# USB_PHY.net
KiCad netlist of a schematic drawn in Altium Designer
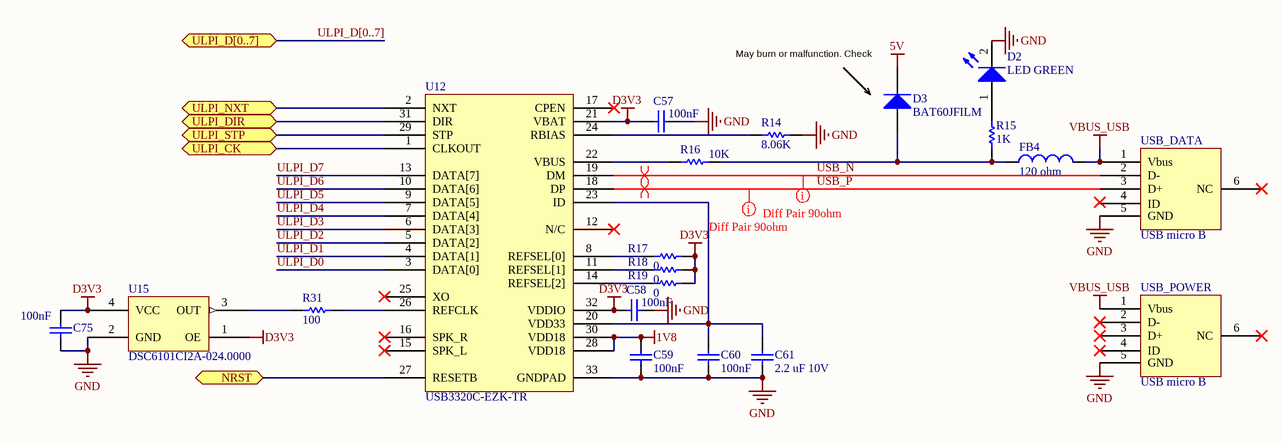
[diagram p0: USB PHY.SchDoc]

(export (version "E")
  (design (tool "Eeschema 10.0.6"))
  (components
    (comp (ref "C57")
      (value "100nF")
      (footprint "0603 Cap")
      (description "CAP CER 0.1UF 16V X7R 0603")
      (fields
        (field (name "MANUFACTURER") "KEMET")
        (field (name "MANUFACTURER PART NUMBER") "C0603C104K4RACTU")
      )
      (libsource (lib "Componentes_base") (part "C0603C104K4RACTU"))
    )
    (comp (ref "C58")
      (value "100nF")
      (footprint "0603 Cap")
      (description "CAP CER 0.1UF 16V X7R 0603")
      (fields
        (field (name "MANUFACTURER") "KEMET")
        (field (name "MANUFACTURER PART NUMBER") "C0603C104K4RACTU")
      )
      (libsource (lib "Componentes_base") (part "C0603C104K4RACTU"))
    )
    (comp (ref "C59")
      (value "100nF")
      (footprint "0603 Cap")
      (description "CAP CER 0.1UF 16V X7R 0603")
      (fields
        (field (name "MANUFACTURER") "KEMET")
        (field (name "MANUFACTURER PART NUMBER") "C0603C104K4RACTU")
      )
      (libsource (lib "Componentes_base") (part "C0603C104K4RACTU"))
    )
    (comp (ref "C60")
      (value "100nF")
      (footprint "0603 Cap")
      (description "CAP CER 0.1UF 16V X7R 0603")
      (fields
        (field (name "MANUFACTURER") "KEMET")
        (field (name "MANUFACTURER PART NUMBER") "C0603C104K4RACTU")
      )
      (libsource (lib "Componentes_base") (part "C0603C104K4RACTU"))
    )
    (comp (ref "C61")
      (value "2.2 uF 10V")
      (footprint "0603 Cap")
      (description "CAP CER 2.2UF 10V X7R 0603")
      (fields
        (field (name "MANUFACTURER") "Samsung Electro-Mechanics America, Inc.")
        (field (name "MANUFACTURER PART NUMBER") "CL10B225KP8NNNC")
      )
      (libsource (lib "Componentes_base") (part "CL10B225KP8NNNC"))
    )
    (comp (ref "C75")
      (value "100nF")
      (footprint "0603 Cap")
      (description "CAP CER 0.1UF 16V X7R 0603")
      (fields
        (field (name "MANUFACTURER") "KEMET")
        (field (name "MANUFACTURER PART NUMBER") "C0603C104K4RACTU")
      )
      (libsource (lib "Componentes_base") (part "C0603C104K4RACTU"))
    )
    (comp (ref "D2")
      (value "LED GREEN")
      (footprint "0603 LED")
      (description "LED GREEN CLEAR 0603 SMD")
      (fields
        (field (name "MANUFACTURER") "Lite-On Inc.")
        (field (name "MANUFACTURER PART NUMBER") "LTST-C191KGKT")
      )
      (libsource (lib "Componentes_base") (part "LTST-C191KGKT"))
    )
    (comp (ref "D3")
      (value "BAT60JFILM")
      (footprint "SODFL250X117-2N")
      (description "DIODE SCHOTTKY 10V 3A SOD323")
      (fields (field (name "MANUFACTURER") "STMicroelectronics"))
      (libsource (lib "Componentes_base") (part "BAT60JFILM"))
    )
    (comp (ref "FB4")
      (value "120 ohm")
      (footprint "INDC1608X08L")
      (description "FERRITE BEAD 120 OHM 0603 1LN")
      (fields
        (field (name "MANUFACTURER") "Murata Electronics North America")
        (field (name "MANUFACTURER PART NUMBER") "BLM18PG121SN1D")
      )
      (libsource (lib "Componentes_base") (part "BLM18PG121SN1D"))
    )
    (comp (ref "R14")
      (value "8.06K")
      (footprint "0603 Res")
      (description "RES SMD 8.06K OHM 1% 1/10W 0603")
      (fields
        (field (name "MANUFACTURER") "Yageo")
        (field (name "MANUFACTURER PART NUMBER") "RC0603FR-078K06L")
      )
      (libsource (lib "Componentes_base") (part "RC0603FR-078K06L"))
    )
    (comp (ref "R15")
      (value "1K")
      (footprint "0603 Res")
      (description "RES SMD 1K OHM 1% 1/10W 0603")
      (fields
        (field (name "MANUFACTURER") "Yageo")
        (field (name "MANUFACTURER PART NUMBER") "RC0603FR-071KL")
      )
      (libsource (lib "Componentes_base") (part "RC0603FR-071KL"))
    )
    (comp (ref "R16")
      (value "10K")
      (footprint "0603 Res")
      (description "RES SMD 10K OHM 1% 1/10W 0603")
      (fields
        (field (name "MANUFACTURER") "Yageo")
        (field (name "MANUFACTURER PART NUMBER") "RC0603FR-0710KL")
      )
      (libsource (lib "Componentes_base") (part "RC0603FR-0710KL"))
    )
    (comp (ref "R17")
      (value "0")
      (footprint "RESC1005X04L")
      (description "RES 0.0 OHM 1/16W JUMP 0402")
      (fields
        (field (name "MANUFACTURER") "Samsung Electro-Mechanics America, Inc")
        (field (name "MANUFACTURER PART NUMBER") "RC1005J000CS")
      )
      (libsource (lib "Componentes_base") (part "RC1005J000CS"))
    )
    (comp (ref "R18")
      (value "0")
      (footprint "RESC1005X04L")
      (description "RES 0.0 OHM 1/16W JUMP 0402")
      (fields
        (field (name "MANUFACTURER") "Samsung Electro-Mechanics America, Inc")
        (field (name "MANUFACTURER PART NUMBER") "RC1005J000CS")
      )
      (libsource (lib "Componentes_base") (part "RC1005J000CS"))
    )
    (comp (ref "R19")
      (value "0")
      (footprint "RESC1005X04L")
      (description "RES 0.0 OHM 1/16W JUMP 0402")
      (fields
        (field (name "MANUFACTURER") "Samsung Electro-Mechanics America, Inc")
        (field (name "MANUFACTURER PART NUMBER") "RC1005J000CS")
      )
      (libsource (lib "Componentes_base") (part "RC1005J000CS"))
    )
    (comp (ref "R31")
      (value "100")
      (footprint "RESC1005X04L")
      (description "RES 100 OHM 1/16W 1% 0402 SMD")
      (fields
        (field (name "MANUFACTURER") "Rohm Semiconductor")
        (field (name "MANUFACTURER PART NUMBER") "MCR01MRTF1000")
      )
      (libsource (lib "Componentes_base") (part "MCR01MRTF1000"))
    )
    (comp (ref "U12")
      (value "USB3320C-EZK-TR")
      (footprint "QFN127P600-8N")
      (description "IC TXRX USB 2.0 FLEXPWR 32QFN")
      (fields (field (name "MANUFACTURER") "Microchip Technology"))
      (libsource (lib "Componentes_base") (part "USB3320C-EZK-TR"))
    )
    (comp (ref "U15")
      (value "DSC6101CI2A-024.0000")
      (footprint "DFN 3.2x2.5")
      (description "ULTRA-LOW POWER,MEMS OSCILLATOR,")
      (fields (field (name "MANUFACTURER") "Microchip Technology"))
      (libsource (lib "Componentes_base") (part "DSC6101CI2A-024.0000"))
    )
    (comp (ref "USB_DATA")
      (value "USB micro B")
      (footprint "USB-MicroB")
      (libsource (lib "B105connectors") (part "USB micro B"))
    )
    (comp (ref "USB_POWER")
      (value "USB micro B")
      (footprint "USB-MicroB")
      (libsource (lib "B105connectors") (part "USB micro B"))
    )
  )
  (nets
    (net (code "1") (name "/NRST") (class "Default")
      (node (ref "U12") (pin "27") (pinfunction "RESETB_27") (pintype "passive"))
    )
    (net (code "2") (name "/ULPI_CK") (class "Default")
      (node (ref "U12") (pin "1") (pinfunction "CLKOUT_1") (pintype "passive"))
    )
    (net (code "3") (name "/ULPI_D0") (class "Default")
      (node (ref "U12") (pin "3") (pinfunction "DATA[0]_3") (pintype "passive"))
    )
    (net (code "4") (name "/ULPI_D1") (class "Default")
      (node (ref "U12") (pin "4") (pinfunction "DATA[1]_4") (pintype "passive"))
    )
    (net (code "5") (name "/ULPI_D2") (class "Default")
      (node (ref "U12") (pin "5") (pinfunction "DATA[2]_5") (pintype "passive"))
    )
    (net (code "6") (name "/ULPI_D3") (class "Default")
      (node (ref "U12") (pin "6") (pinfunction "DATA[3]_6") (pintype "passive"))
    )
    (net (code "7") (name "/ULPI_D4") (class "Default")
      (node (ref "U12") (pin "7") (pinfunction "DATA[4]_7") (pintype "passive"))
    )
    (net (code "8") (name "/ULPI_D5") (class "Default")
      (node (ref "U12") (pin "9") (pinfunction "DATA[5]_9") (pintype "passive"))
    )
    (net (code "9") (name "/ULPI_D6") (class "Default")
      (node (ref "U12") (pin "10") (pinfunction "DATA[6]_10") (pintype "passive"))
    )
    (net (code "10") (name "/ULPI_D7") (class "Default")
      (node (ref "U12") (pin "13") (pinfunction "DATA[7]_13") (pintype "passive"))
    )
    (net (code "11") (name "/ULPI_DIR") (class "Default")
      (node (ref "U12") (pin "31") (pinfunction "DIR_31") (pintype "passive"))
    )
    (net (code "13") (name "/ULPI_NXT") (class "Default")
      (node (ref "U12") (pin "2") (pinfunction "NXT_2") (pintype "passive"))
    )
    (net (code "14") (name "/ULPI_STP") (class "Default")
      (node (ref "U12") (pin "29") (pinfunction "STP_29") (pintype "passive"))
    )
    (net (code "15") (name "/USB_N") (class "Default")
      (node (ref "U12") (pin "19") (pinfunction "DM_19") (pintype "passive"))
      (node (ref "USB_DATA") (pin "2") (pinfunction "D-_2") (pintype "passive"))
    )
    (net (code "16") (name "/USB_P") (class "Default")
      (node (ref "U12") (pin "18") (pinfunction "DP_18") (pintype "passive"))
      (node (ref "USB_DATA") (pin "3") (pinfunction "D+_3") (pintype "passive"))
    )
    (net (code "17") (name "1V8") (class "Default")
      (node (ref "C59") (pin "2") (pinfunction "2_2") (pintype "passive"))
      (node (ref "U12") (pin "28") (pinfunction "VDD18_28") (pintype "passive"))
      (node (ref "U12") (pin "30") (pinfunction "VDD18_30") (pintype "passive"))
    )
    (net (code "18") (name "5V") (class "Default")
      (node (ref "D3") (pin "1") (pinfunction "K_1") (pintype "passive"))
    )
    (net (code "19") (name "D3V3") (class "Default")
      (node (ref "C57") (pin "2") (pinfunction "2_2") (pintype "passive"))
      (node (ref "C58") (pin "2") (pinfunction "2_2") (pintype "passive"))
      (node (ref "C75") (pin "2") (pinfunction "2_2") (pintype "passive"))
      (node (ref "R17") (pin "2") (pinfunction "2_2") (pintype "passive"))
      (node (ref "R18") (pin "2") (pinfunction "2_2") (pintype "passive"))
      (node (ref "R19") (pin "2") (pinfunction "2_2") (pintype "passive"))
      (node (ref "U12") (pin "21") (pinfunction "VBAT_21") (pintype "passive"))
      (node (ref "U12") (pin "32") (pinfunction "VDDIO_32") (pintype "passive"))
      (node (ref "U15") (pin "1") (pinfunction "OE_1") (pintype "passive"))
      (node (ref "U15") (pin "4") (pinfunction "VCC_4") (pintype "power_in"))
    )
    (net (code "20") (name "GND") (class "Default")
      (node (ref "C57") (pin "1") (pinfunction "1_1") (pintype "passive"))
      (node (ref "C58") (pin "1") (pinfunction "1_1") (pintype "passive"))
      (node (ref "C59") (pin "1") (pinfunction "1_1") (pintype "passive"))
      (node (ref "C60") (pin "1") (pinfunction "1_1") (pintype "passive"))
      (node (ref "C61") (pin "1") (pinfunction "1_1") (pintype "passive"))
      (node (ref "C75") (pin "1") (pinfunction "1_1") (pintype "passive"))
      (node (ref "D2") (pin "2") (pinfunction "C_2") (pintype "passive"))
      (node (ref "R14") (pin "2") (pinfunction "2_2") (pintype "passive"))
      (node (ref "U12") (pin "33") (pinfunction "GNDPAD_33") (pintype "passive"))
      (node (ref "U15") (pin "2") (pinfunction "GND_2") (pintype "power_in"))
      (node (ref "USB_DATA") (pin "5") (pinfunction "GND_5") (pintype "passive"))
      (node (ref "USB_POWER") (pin "5") (pinfunction "GND_5") (pintype "passive"))
    )
    (net (code "21") (name "Net-(D2-A)") (class "Default")
      (node (ref "D2") (pin "1") (pinfunction "A_1") (pintype "passive"))
      (node (ref "R15") (pin "2") (pinfunction "2_2") (pintype "passive"))
    )
    (net (code "22") (name "Net-(D3-A)") (class "Default")
      (node (ref "D3") (pin "2") (pinfunction "A_2") (pintype "passive"))
      (node (ref "FB4") (pin "1") (pinfunction "1_1") (pintype "passive"))
      (node (ref "R15") (pin "1") (pinfunction "1_1") (pintype "passive"))
      (node (ref "R16") (pin "2") (pinfunction "2_2") (pintype "passive"))
    )
    (net (code "23") (name "Net-(U12-ID)") (class "Default")
      (node (ref "C60") (pin "2") (pinfunction "2_2") (pintype "passive"))
      (node (ref "C61") (pin "2") (pinfunction "2_2") (pintype "passive"))
      (node (ref "U12") (pin "20") (pinfunction "VDD33_20") (pintype "passive"))
      (node (ref "U12") (pin "23") (pinfunction "ID_23") (pintype "passive"))
    )
    (net (code "24") (name "Net-(U12-RBIAS)") (class "Default")
      (node (ref "R14") (pin "1") (pinfunction "1_1") (pintype "passive"))
      (node (ref "U12") (pin "24") (pinfunction "RBIAS_24") (pintype "passive"))
    )
    (net (code "25") (name "Net-(U12-REFCLK)") (class "Default")
      (node (ref "R31") (pin "2") (pinfunction "2_2") (pintype "passive"))
      (node (ref "U12") (pin "26") (pinfunction "REFCLK_26") (pintype "passive"))
    )
    (net (code "26") (name "Net-(U12-REFSEL[0])") (class "Default")
      (node (ref "R17") (pin "1") (pinfunction "1_1") (pintype "passive"))
      (node (ref "U12") (pin "8") (pinfunction "REFSEL[0]_8") (pintype "passive"))
    )
    (net (code "27") (name "Net-(U12-REFSEL[1])") (class "Default")
      (node (ref "R18") (pin "1") (pinfunction "1_1") (pintype "passive"))
      (node (ref "U12") (pin "11") (pinfunction "REFSEL[1]_11") (pintype "passive"))
    )
    (net (code "28") (name "Net-(U12-REFSEL[2])") (class "Default")
      (node (ref "R19") (pin "1") (pinfunction "1_1") (pintype "passive"))
      (node (ref "U12") (pin "14") (pinfunction "REFSEL[2]_14") (pintype "passive"))
    )
    (net (code "29") (name "Net-(U12-VBUS)") (class "Default")
      (node (ref "R16") (pin "1") (pinfunction "1_1") (pintype "passive"))
      (node (ref "U12") (pin "22") (pinfunction "VBUS_22") (pintype "passive"))
    )
    (net (code "30") (name "Net-(U15-OUT)") (class "Default")
      (node (ref "R31") (pin "1") (pinfunction "1_1") (pintype "passive"))
      (node (ref "U15") (pin "3") (pinfunction "OUT_3") (pintype "output"))
    )
    (net (code "31") (name "VBUS_USB") (class "Default")
      (node (ref "FB4") (pin "2") (pinfunction "2_2") (pintype "passive"))
      (node (ref "USB_DATA") (pin "1") (pinfunction "Vbus_1") (pintype "passive"))
      (node (ref "USB_POWER") (pin "1") (pinfunction "Vbus_1") (pintype "passive"))
    )
    (net (code "32") (name "unconnected-(U12-CPEN-Pad17)") (class "Default")
      (node (ref "U12") (pin "17") (pinfunction "CPEN_17") (pintype "passive+no_connect"))
    )
    (net (code "33") (name "unconnected-(U12-N{slash}C-Pad12)") (class "Default")
      (node (ref "U12") (pin "12") (pinfunction "N/C_12") (pintype "passive+no_connect"))
    )
    (net (code "34") (name "unconnected-(U12-SPK_L-Pad15)") (class "Default")
      (node (ref "U12") (pin "15") (pinfunction "SPK_L_15") (pintype "passive+no_connect"))
    )
    (net (code "35") (name "unconnected-(U12-SPK_R-Pad16)") (class "Default")
      (node (ref "U12") (pin "16") (pinfunction "SPK_R_16") (pintype "passive+no_connect"))
    )
    (net (code "36") (name "unconnected-(U12-XO-Pad25)") (class "Default")
      (node (ref "U12") (pin "25") (pinfunction "XO_25") (pintype "passive+no_connect"))
    )
    (net (code "37") (name "unconnected-(USB_DATA-ID-Pad4)") (class "Default")
      (node (ref "USB_DATA") (pin "4") (pinfunction "ID_4") (pintype "passive"))
    )
    (net (code "38") (name "unconnected-(USB_DATA-NC-Pad6)") (class "Default")
      (node (ref "USB_DATA") (pin "6") (pinfunction "NC_6") (pintype "passive+no_connect"))
    )
    (net (code "39") (name "unconnected-(USB_POWER-D+-Pad3)") (class "Default")
      (node (ref "USB_POWER") (pin "3") (pinfunction "D+_3") (pintype "passive+no_connect"))
    )
    (net (code "40") (name "unconnected-(USB_POWER-D--Pad2)") (class "Default")
      (node (ref "USB_POWER") (pin "2") (pinfunction "D-_2") (pintype "passive+no_connect"))
    )
    (net (code "41") (name "unconnected-(USB_POWER-ID-Pad4)") (class "Default")
      (node (ref "USB_POWER") (pin "4") (pinfunction "ID_4") (pintype "passive+no_connect"))
    )
    (net (code "42") (name "unconnected-(USB_POWER-NC-Pad6)") (class "Default")
      (node (ref "USB_POWER") (pin "6") (pinfunction "NC_6") (pintype "passive+no_connect"))
    )
  )
)
